# Schematic.net
KiCad netlist of a schematic drawn in Altium Designer
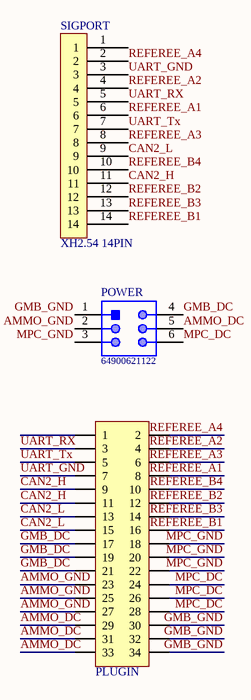
[diagram p0: Schematic.SchDoc]

(export (version "E")
  (design (tool "Eeschema 10.0.6"))
  (components
    (comp (ref "PLUGIN")
      (value "Header 2X11")
      (footprint "IDC2.54-LI-2x17P")
      (description "17*2P接插件")
      (fields (field (name "版权归属") "封装库来自淘宝 ID：黄晶宝石"))
      (libsource (lib "5.4 - 接插件-脚距2.54 (100mil) ") (part "Header 17X2"))
    )
    (comp (ref "POWER")
      (value "64900621122")
      (footprint "64900621122")
      (description "THT Male Header WR-MPC4, Vertical, Dual Row, pitch 4.2 mm, 6 pins")
      (fields (field (name "MANUFACTURER") "Wurth Elektronik") (field (name "PUBLISHER") "WurthElektronik"))
      (libsource (lib "Altium Content Vault") (part "WE-CN-2P-M-R6_A"))
    )
    (comp (ref "SIGPORT")
      (value "XH2.54 14PIN")
      (footprint "DC-2.54-L-Z-14P")
      (libsource (lib "NewInfLibSc") (part "XH2.54 14PIN"))
    )
  )
  (nets
    (net (code "1") (name "/AMMO_DC") (class "Default")
      (node (ref "PLUGIN") (pin "29") (pinfunction "29_29") (pintype "passive"))
      (node (ref "PLUGIN") (pin "31") (pinfunction "31_31") (pintype "passive"))
      (node (ref "PLUGIN") (pin "33") (pinfunction "33_33") (pintype "passive"))
      (node (ref "POWER") (pin "5") (pinfunction "5_5") (pintype "passive"))
    )
    (net (code "2") (name "/AMMO_GND") (class "Default")
      (node (ref "PLUGIN") (pin "23") (pinfunction "23_23") (pintype "passive"))
      (node (ref "PLUGIN") (pin "25") (pinfunction "25_25") (pintype "passive"))
      (node (ref "PLUGIN") (pin "27") (pinfunction "27_27") (pintype "passive"))
      (node (ref "POWER") (pin "2") (pinfunction "2_2") (pintype "passive"))
    )
    (net (code "3") (name "/CAN2_H") (class "Default")
      (node (ref "PLUGIN") (pin "11") (pinfunction "11_11") (pintype "passive"))
      (node (ref "PLUGIN") (pin "9") (pinfunction "9_9") (pintype "passive"))
      (node (ref "SIGPORT") (pin "11") (pinfunction "11_11") (pintype "passive"))
    )
    (net (code "4") (name "/CAN2_L") (class "Default")
      (node (ref "PLUGIN") (pin "13") (pinfunction "13_13") (pintype "passive"))
      (node (ref "PLUGIN") (pin "15") (pinfunction "15_15") (pintype "passive"))
      (node (ref "SIGPORT") (pin "9") (pinfunction "9_9") (pintype "passive"))
    )
    (net (code "5") (name "/GMB_DC") (class "Default")
      (node (ref "PLUGIN") (pin "17") (pinfunction "17_17") (pintype "passive"))
      (node (ref "PLUGIN") (pin "19") (pinfunction "19_19") (pintype "passive"))
      (node (ref "PLUGIN") (pin "21") (pinfunction "21_21") (pintype "passive"))
      (node (ref "POWER") (pin "4") (pinfunction "4_4") (pintype "passive"))
    )
    (net (code "6") (name "/GMB_GND") (class "Default")
      (node (ref "PLUGIN") (pin "30") (pinfunction "30_30") (pintype "passive"))
      (node (ref "PLUGIN") (pin "32") (pinfunction "32_32") (pintype "passive"))
      (node (ref "PLUGIN") (pin "34") (pinfunction "34_34") (pintype "passive"))
      (node (ref "POWER") (pin "1") (pinfunction "1_1") (pintype "passive"))
    )
    (net (code "7") (name "/MPC_DC") (class "Default")
      (node (ref "PLUGIN") (pin "24") (pinfunction "24_24") (pintype "passive"))
      (node (ref "PLUGIN") (pin "26") (pinfunction "26_26") (pintype "passive"))
      (node (ref "PLUGIN") (pin "28") (pinfunction "28_28") (pintype "passive"))
      (node (ref "POWER") (pin "6") (pinfunction "6_6") (pintype "passive"))
    )
    (net (code "8") (name "/MPC_GND") (class "Default")
      (node (ref "PLUGIN") (pin "18") (pinfunction "18_18") (pintype "passive"))
      (node (ref "PLUGIN") (pin "20") (pinfunction "20_20") (pintype "passive"))
      (node (ref "PLUGIN") (pin "22") (pinfunction "22_22") (pintype "passive"))
      (node (ref "POWER") (pin "3") (pinfunction "3_3") (pintype "passive"))
    )
    (net (code "9") (name "/REFEREE_A1") (class "Default")
      (node (ref "PLUGIN") (pin "8") (pinfunction "8_8") (pintype "passive"))
      (node (ref "SIGPORT") (pin "6") (pinfunction "6_6") (pintype "passive"))
    )
    (net (code "10") (name "/REFEREE_A2") (class "Default")
      (node (ref "PLUGIN") (pin "4") (pinfunction "4_4") (pintype "passive"))
      (node (ref "SIGPORT") (pin "4") (pinfunction "4_4") (pintype "passive"))
    )
    (net (code "11") (name "/REFEREE_A3") (class "Default")
      (node (ref "PLUGIN") (pin "6") (pinfunction "6_6") (pintype "passive"))
      (node (ref "SIGPORT") (pin "8") (pinfunction "8_8") (pintype "passive"))
    )
    (net (code "12") (name "/REFEREE_A4") (class "Default")
      (node (ref "PLUGIN") (pin "2") (pinfunction "2_2") (pintype "passive"))
      (node (ref "SIGPORT") (pin "2") (pinfunction "2_2") (pintype "passive"))
    )
    (net (code "13") (name "/REFEREE_B1") (class "Default")
      (node (ref "PLUGIN") (pin "16") (pinfunction "16_16") (pintype "passive"))
      (node (ref "SIGPORT") (pin "14") (pinfunction "14_14") (pintype "passive"))
    )
    (net (code "14") (name "/REFEREE_B2") (class "Default")
      (node (ref "PLUGIN") (pin "12") (pinfunction "12_12") (pintype "passive"))
      (node (ref "SIGPORT") (pin "12") (pinfunction "12_12") (pintype "passive"))
    )
    (net (code "15") (name "/REFEREE_B3") (class "Default")
      (node (ref "PLUGIN") (pin "14") (pinfunction "14_14") (pintype "passive"))
      (node (ref "SIGPORT") (pin "13") (pinfunction "13_13") (pintype "passive"))
    )
    (net (code "16") (name "/REFEREE_B4") (class "Default")
      (node (ref "PLUGIN") (pin "10") (pinfunction "10_10") (pintype "passive"))
      (node (ref "SIGPORT") (pin "10") (pinfunction "10_10") (pintype "passive"))
    )
    (net (code "17") (name "/UART_GND") (class "Default")
      (node (ref "PLUGIN") (pin "7") (pinfunction "7_7") (pintype "passive"))
      (node (ref "SIGPORT") (pin "3") (pinfunction "3_3") (pintype "passive"))
    )
    (net (code "18") (name "/UART_RX") (class "Default")
      (node (ref "PLUGIN") (pin "3") (pinfunction "3_3") (pintype "passive"))
      (node (ref "SIGPORT") (pin "5") (pinfunction "5_5") (pintype "passive"))
    )
    (net (code "19") (name "/UART_Tx") (class "Default")
      (node (ref "PLUGIN") (pin "5") (pinfunction "5_5") (pintype "passive"))
      (node (ref "SIGPORT") (pin "7") (pinfunction "7_7") (pintype "passive"))
    )
    (net (code "20") (name "unconnected-(PLUGIN-Pad1)") (class "Default")
      (node (ref "PLUGIN") (pin "1") (pinfunction "1_1") (pintype "passive"))
    )
    (net (code "21") (name "unconnected-(SIGPORT-Pad1)") (class "Default")
      (node (ref "SIGPORT") (pin "1") (pinfunction "1_1") (pintype "passive"))
    )
  )
)
